# SCH_Handheld-arduino-game-console_2025-0.net
KiCad netlist of a schematic drawn in EasyEDA
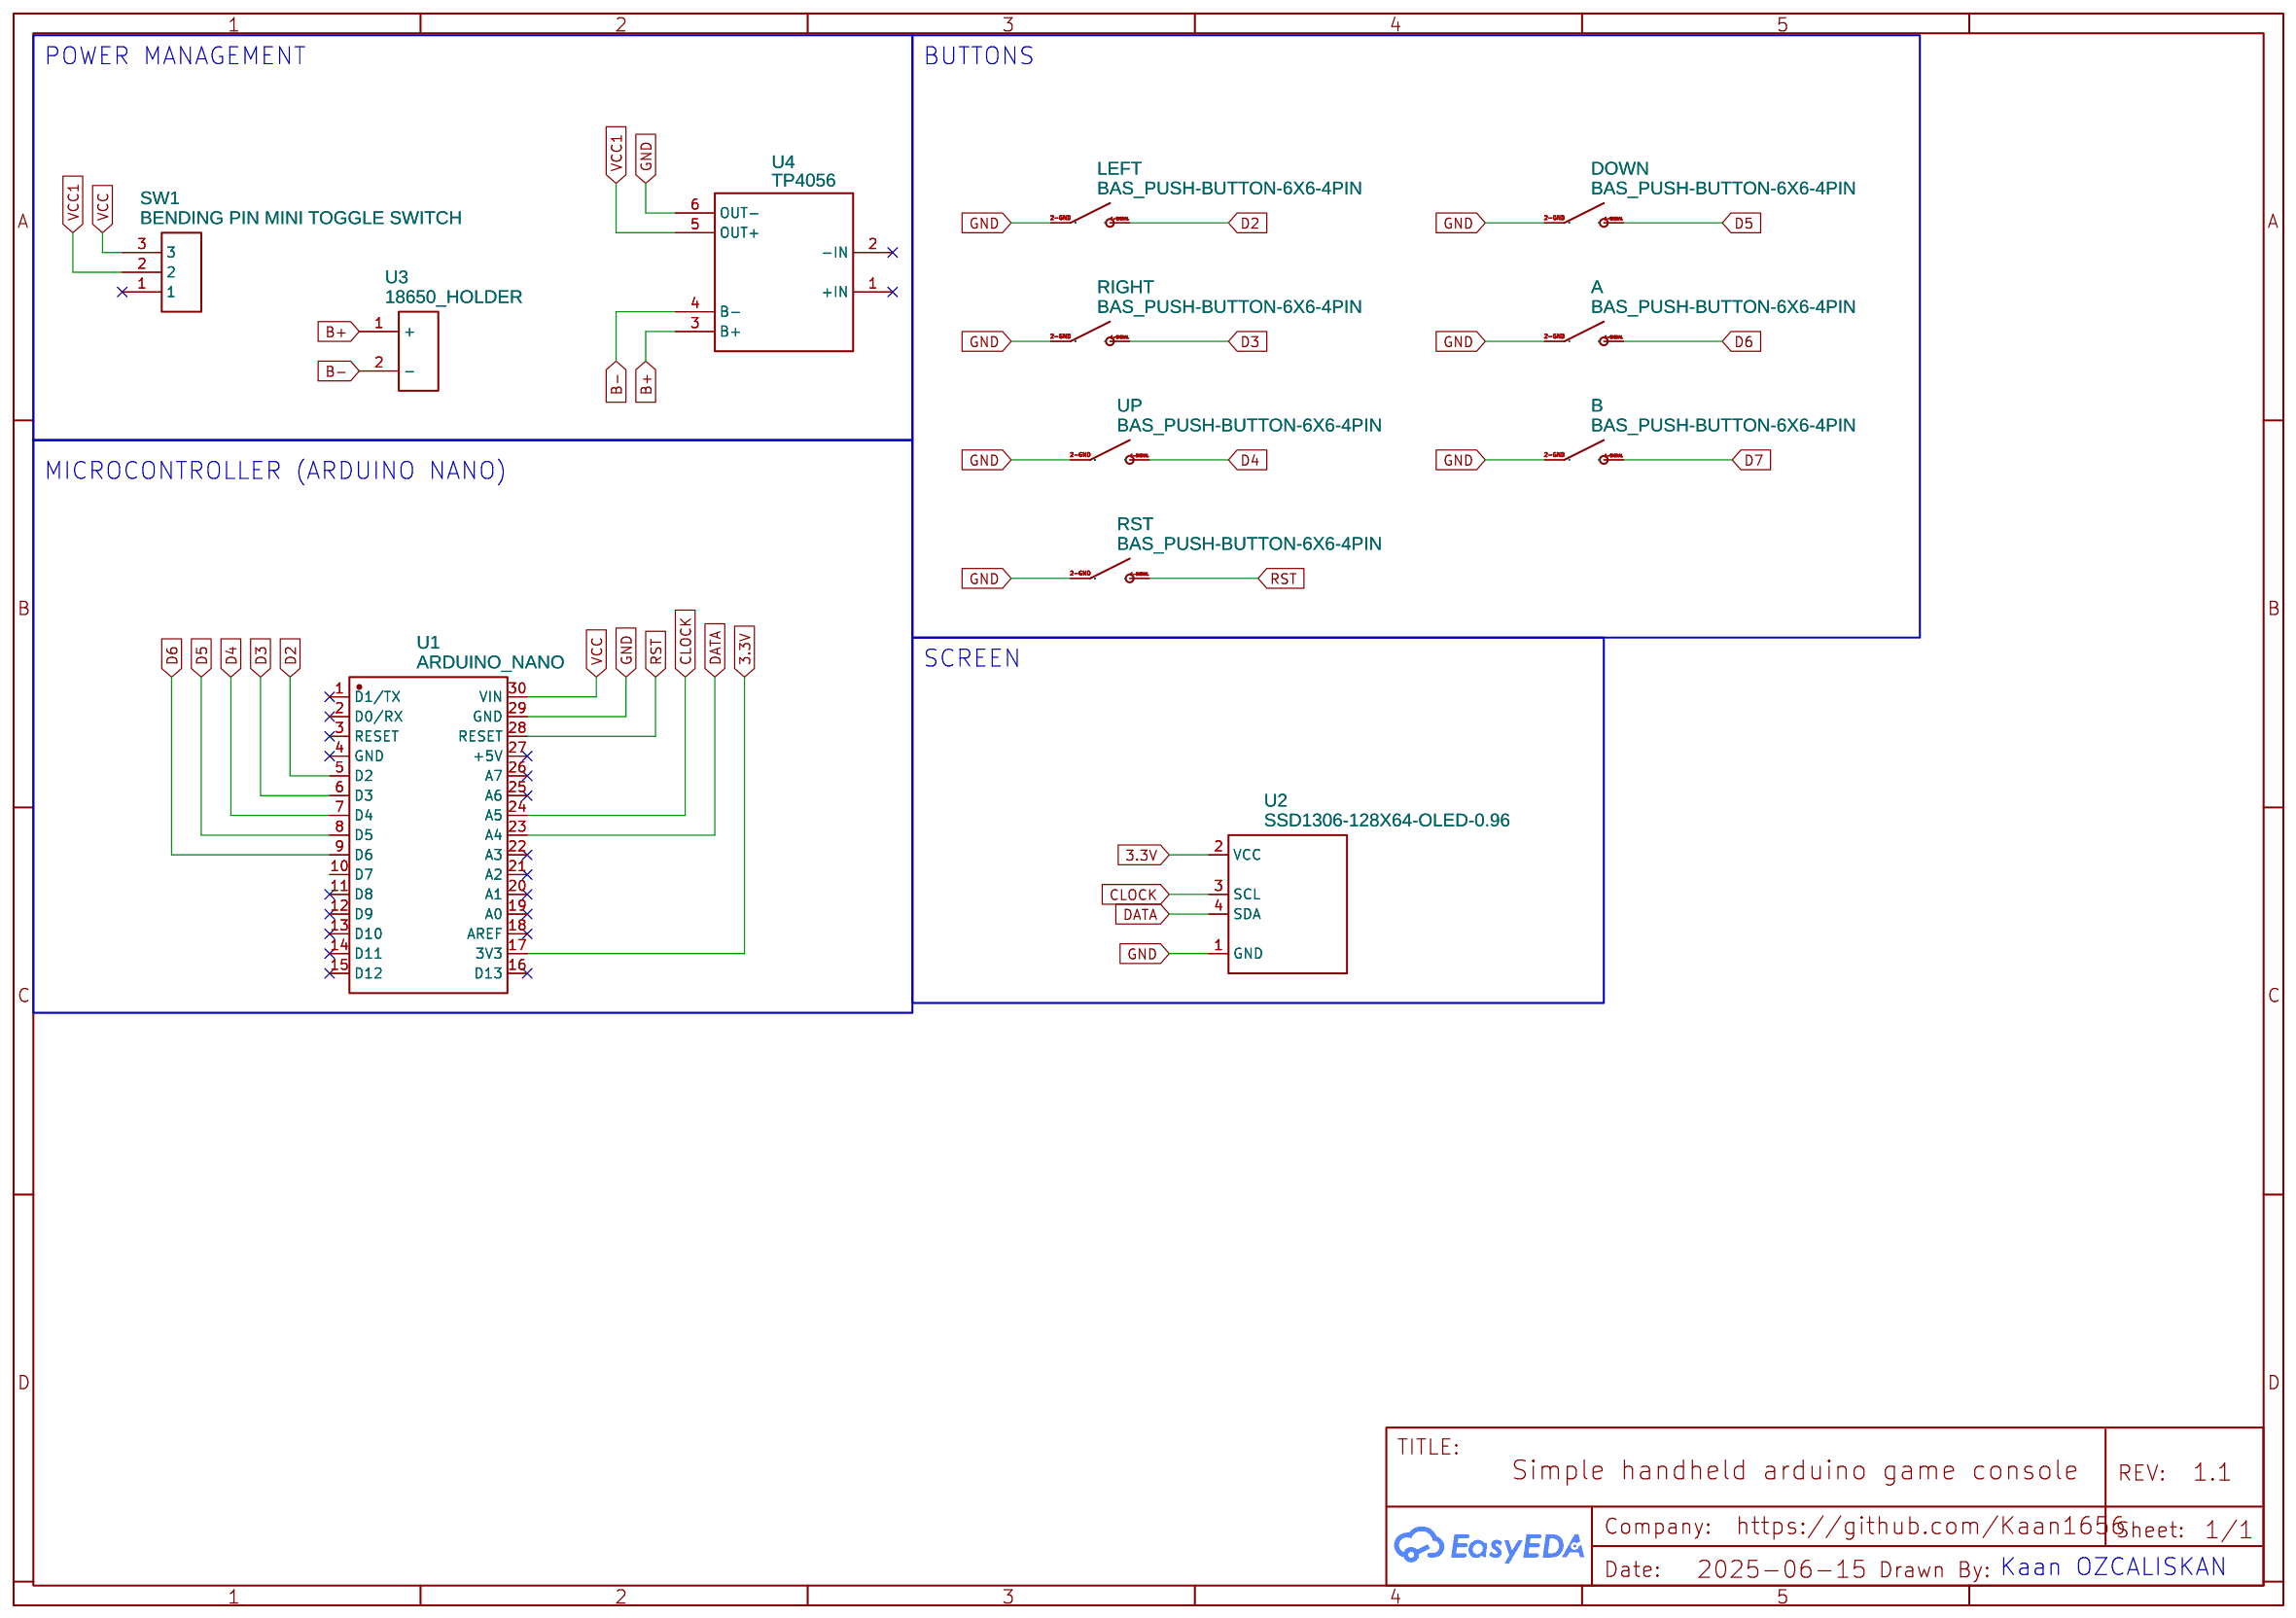
[diagram p0: schematic sheet]

(export (version "E")
  (design (tool "Eeschema 10.0.6"))
  (components
    (comp (ref "A")
      (value "BAS_PUSH-BUTTON-6X6-4PIN")
      (fields (field (name "Manufacturer Part") "?"))
      (libsource (lib "") (part "Unknown_0_-806"))
    )
    (comp (ref "B")
      (value "BAS_PUSH-BUTTON-6X6-4PIN")
      (fields (field (name "Manufacturer Part") "Tact Push Button Micro Switch 6x6 4PIN"))
      (libsource (lib "") (part "BAS_PUSH-BUTTON-6X6-4PIN_6"))
    )
    (comp (ref "DOWN")
      (value "BAS_PUSH-BUTTON-6X6-4PIN")
      (fields (field (name "Manufacturer Part") "Tact Push Button Micro Switch 6x6 4PIN"))
      (libsource (lib "") (part "BAS_PUSH-BUTTON-6X6-4PIN"))
    )
    (comp (ref "LEFT")
      (value "BAS_PUSH-BUTTON-6X6-4PIN")
      (fields (field (name "Manufacturer Part") "Tact Push Button Micro Switch 6x6 4PIN"))
      (libsource (lib "") (part "BAS_PUSH-BUTTON-6X6-4PIN_5"))
    )
    (comp (ref "RIGHT")
      (value "BAS_PUSH-BUTTON-6X6-4PIN")
      (fields (field (name "Manufacturer Part") "Tact Push Button Micro Switch 6x6 4PIN"))
      (libsource (lib "") (part "BAS_PUSH-BUTTON-6X6-4PIN_4"))
    )
    (comp (ref "RST")
      (value "BAS_PUSH-BUTTON-6X6-4PIN")
      (fields (field (name "Manufacturer Part") "Tact Push Button Micro Switch 6x6 4PIN"))
      (libsource (lib "") (part "BAS_PUSH-BUTTON-6X6-4PIN_2"))
    )
    (comp (ref "SW1")
      (value "BENDING PIN MINI TOGGLE SWITCH")
      (fields
        (field (name "Manufacturer Part") "SS12D06")
        (field (name "Manufacturer") "Dongguan Kaifeng Electronic Technology Limited")
      )
      (libsource (lib "") (part "BENDING PIN MINI TOGGLE SWITCH (1P2T) SPDT SLIDE SWITCH GUKI"))
    )
    (comp (ref "U1") (value "ARDUINO_NANO") (libsource (lib "") (part "ARDUINO_NANO")))
    (comp (ref "U2")
      (value "SSD1306-128X64-OLED-0.96")
      (libsource (lib "") (part "SSD1306-128X64-OLED-0.96"))
    )
    (comp (ref "U3") (value "18650_HOLDER") (libsource (lib "") (part "18650_HOLDER")))
    (comp (ref "U4") (value "TP4056") (libsource (lib "") (part "TP4056")))
    (comp (ref "UP")
      (value "BAS_PUSH-BUTTON-6X6-4PIN")
      (fields (field (name "Manufacturer Part") "Tact Push Button Micro Switch 6x6 4PIN"))
      (libsource (lib "") (part "BAS_PUSH-BUTTON-6X6-4PIN_1"))
    )
  )
  (nets
    (net (code "1") (name "3.3V") (class "Default")
      (node (ref "U1") (pin "17") (pinfunction "3V3_17") (pintype "unspecified"))
      (node (ref "U2") (pin "2") (pinfunction "VCC_2") (pintype "input"))
    )
    (net (code "2") (name "B+") (class "Default")
      (node (ref "U3") (pin "1") (pinfunction "+_1") (pintype "unspecified"))
      (node (ref "U4") (pin "3") (pinfunction "B+_3") (pintype "unspecified"))
    )
    (net (code "3") (name "B-") (class "Default")
      (node (ref "U3") (pin "2") (pinfunction "-_2") (pintype "unspecified"))
      (node (ref "U4") (pin "4") (pinfunction "B-_4") (pintype "unspecified"))
    )
    (net (code "4") (name "CLOCK") (class "Default")
      (node (ref "U1") (pin "24") (pinfunction "A5_24") (pintype "unspecified"))
      (node (ref "U2") (pin "3") (pinfunction "SCL_3") (pintype "passive"))
    )
    (net (code "5") (name "D2") (class "Default")
      (node (ref "LEFT") (pin "1-SIGNAL") (pinfunction "1_1-SIGNAL") (pintype "unspecified"))
      (node (ref "U1") (pin "5") (pinfunction "D2_5") (pintype "unspecified"))
    )
    (net (code "6") (name "D3") (class "Default")
      (node (ref "RIGHT") (pin "1-SIGNAL") (pinfunction "1_1-SIGNAL") (pintype "unspecified"))
      (node (ref "U1") (pin "6") (pinfunction "D3_6") (pintype "unspecified"))
    )
    (net (code "7") (name "D4") (class "Default")
      (node (ref "U1") (pin "7") (pinfunction "D4_7") (pintype "unspecified"))
      (node (ref "UP") (pin "1-SIGNAL") (pinfunction "1_1-SIGNAL") (pintype "unspecified"))
    )
    (net (code "8") (name "D5") (class "Default")
      (node (ref "DOWN") (pin "1-SIGNAL") (pinfunction "1_1-SIGNAL") (pintype "unspecified"))
      (node (ref "U1") (pin "8") (pinfunction "D5_8") (pintype "unspecified"))
    )
    (net (code "9") (name "D6") (class "Default")
      (node (ref "A") (pin "1-SIGNAL") (pinfunction "1_1-SIGNAL") (pintype "unspecified"))
      (node (ref "U1") (pin "9") (pinfunction "D6_9") (pintype "unspecified"))
    )
    (net (code "10") (name "D7") (class "Default")
      (node (ref "B") (pin "1-SIGNAL") (pinfunction "1_1-SIGNAL") (pintype "unspecified"))
    )
    (net (code "11") (name "DATA") (class "Default")
      (node (ref "U1") (pin "23") (pinfunction "A4_23") (pintype "unspecified"))
      (node (ref "U2") (pin "4") (pinfunction "SDA_4") (pintype "passive"))
    )
    (net (code "12") (name "GND") (class "Default")
      (node (ref "A") (pin "2-GND") (pinfunction "2_2-GND") (pintype "unspecified"))
      (node (ref "B") (pin "2-GND") (pinfunction "2_2-GND") (pintype "unspecified"))
      (node (ref "DOWN") (pin "2-GND") (pinfunction "2_2-GND") (pintype "unspecified"))
      (node (ref "LEFT") (pin "2-GND") (pinfunction "2_2-GND") (pintype "unspecified"))
      (node (ref "RIGHT") (pin "2-GND") (pinfunction "2_2-GND") (pintype "unspecified"))
      (node (ref "RST") (pin "2-GND") (pinfunction "2_2-GND") (pintype "unspecified"))
      (node (ref "U1") (pin "29") (pinfunction "GND_29") (pintype "unspecified"))
      (node (ref "U2") (pin "1") (pinfunction "GND_1") (pintype "input"))
      (node (ref "U4") (pin "6") (pinfunction "OUT-_6") (pintype "unspecified"))
      (node (ref "UP") (pin "2-GND") (pinfunction "2_2-GND") (pintype "unspecified"))
    )
    (net (code "13") (name "RST") (class "Default")
      (node (ref "RST") (pin "1-SIGNAL") (pinfunction "1_1-SIGNAL") (pintype "unspecified"))
      (node (ref "U1") (pin "28") (pinfunction "RESET_28") (pintype "unspecified"))
    )
    (net (code "14") (name "VCC") (class "Default")
      (node (ref "SW1") (pin "3") (pinfunction "3_3") (pintype "unspecified"))
      (node (ref "U1") (pin "30") (pinfunction "VIN_30") (pintype "unspecified"))
    )
    (net (code "15") (name "VCC1") (class "Default")
      (node (ref "SW1") (pin "2") (pinfunction "2_2") (pintype "unspecified"))
      (node (ref "U4") (pin "5") (pinfunction "OUT+_5") (pintype "unspecified"))
    )
    (net (code "16") (name "unconnected-(SW1-Pad1)") (class "Default")
      (node (ref "SW1") (pin "1") (pinfunction "1_1") (pintype "unspecified+no_connect"))
    )
    (net (code "17") (name "unconnected-(U1-+5V-Pad27)") (class "Default")
      (node (ref "U1") (pin "27") (pinfunction "+5V_27") (pintype "unspecified+no_connect"))
    )
    (net (code "18") (name "unconnected-(U1-A0-Pad19)") (class "Default")
      (node (ref "U1") (pin "19") (pinfunction "A0_19") (pintype "unspecified+no_connect"))
    )
    (net (code "19") (name "unconnected-(U1-A1-Pad20)") (class "Default")
      (node (ref "U1") (pin "20") (pinfunction "A1_20") (pintype "unspecified+no_connect"))
    )
    (net (code "20") (name "unconnected-(U1-A2-Pad21)") (class "Default")
      (node (ref "U1") (pin "21") (pinfunction "A2_21") (pintype "unspecified+no_connect"))
    )
    (net (code "21") (name "unconnected-(U1-A3-Pad22)") (class "Default")
      (node (ref "U1") (pin "22") (pinfunction "A3_22") (pintype "unspecified+no_connect"))
    )
    (net (code "22") (name "unconnected-(U1-A6-Pad25)") (class "Default")
      (node (ref "U1") (pin "25") (pinfunction "A6_25") (pintype "unspecified+no_connect"))
    )
    (net (code "23") (name "unconnected-(U1-A7-Pad26)") (class "Default")
      (node (ref "U1") (pin "26") (pinfunction "A7_26") (pintype "unspecified+no_connect"))
    )
    (net (code "24") (name "unconnected-(U1-AREF-Pad18)") (class "Default")
      (node (ref "U1") (pin "18") (pinfunction "AREF_18") (pintype "unspecified+no_connect"))
    )
    (net (code "25") (name "unconnected-(U1-D0{slash}RX-Pad2)") (class "Default")
      (node (ref "U1") (pin "2") (pinfunction "D0/RX_2") (pintype "unspecified+no_connect"))
    )
    (net (code "26") (name "unconnected-(U1-D1{slash}TX-Pad1)") (class "Default")
      (node (ref "U1") (pin "1") (pinfunction "D1/TX_1") (pintype "unspecified+no_connect"))
    )
    (net (code "27") (name "unconnected-(U1-D7-Pad10)") (class "Default")
      (node (ref "U1") (pin "10") (pinfunction "D7_10") (pintype "unspecified"))
    )
    (net (code "28") (name "unconnected-(U1-D8-Pad11)") (class "Default")
      (node (ref "U1") (pin "11") (pinfunction "D8_11") (pintype "unspecified+no_connect"))
    )
    (net (code "29") (name "unconnected-(U1-D9-Pad12)") (class "Default")
      (node (ref "U1") (pin "12") (pinfunction "D9_12") (pintype "unspecified+no_connect"))
    )
    (net (code "30") (name "unconnected-(U1-D10-Pad13)") (class "Default")
      (node (ref "U1") (pin "13") (pinfunction "D10_13") (pintype "unspecified+no_connect"))
    )
    (net (code "31") (name "unconnected-(U1-D11-Pad14)") (class "Default")
      (node (ref "U1") (pin "14") (pinfunction "D11_14") (pintype "unspecified+no_connect"))
    )
    (net (code "32") (name "unconnected-(U1-D12-Pad15)") (class "Default")
      (node (ref "U1") (pin "15") (pinfunction "D12_15") (pintype "unspecified+no_connect"))
    )
    (net (code "33") (name "unconnected-(U1-D13-Pad16)") (class "Default")
      (node (ref "U1") (pin "16") (pinfunction "D13_16") (pintype "unspecified+no_connect"))
    )
    (net (code "34") (name "unconnected-(U1-GND-Pad4)") (class "Default")
      (node (ref "U1") (pin "4") (pinfunction "GND_4") (pintype "unspecified+no_connect"))
    )
    (net (code "35") (name "unconnected-(U1-RESET-Pad3)") (class "Default")
      (node (ref "U1") (pin "3") (pinfunction "RESET_3") (pintype "unspecified+no_connect"))
    )
    (net (code "36") (name "unconnected-(U4-+IN-Pad1)") (class "Default")
      (node (ref "U4") (pin "1") (pinfunction "+IN_1") (pintype "unspecified+no_connect"))
    )
    (net (code "37") (name "unconnected-(U4--IN-Pad2)") (class "Default")
      (node (ref "U4") (pin "2") (pinfunction "-IN_2") (pintype "unspecified+no_connect"))
    )
  )
)
